# Sinewave_PWM_controller.net
KiCad netlist of a schematic drawn in Altium Designer
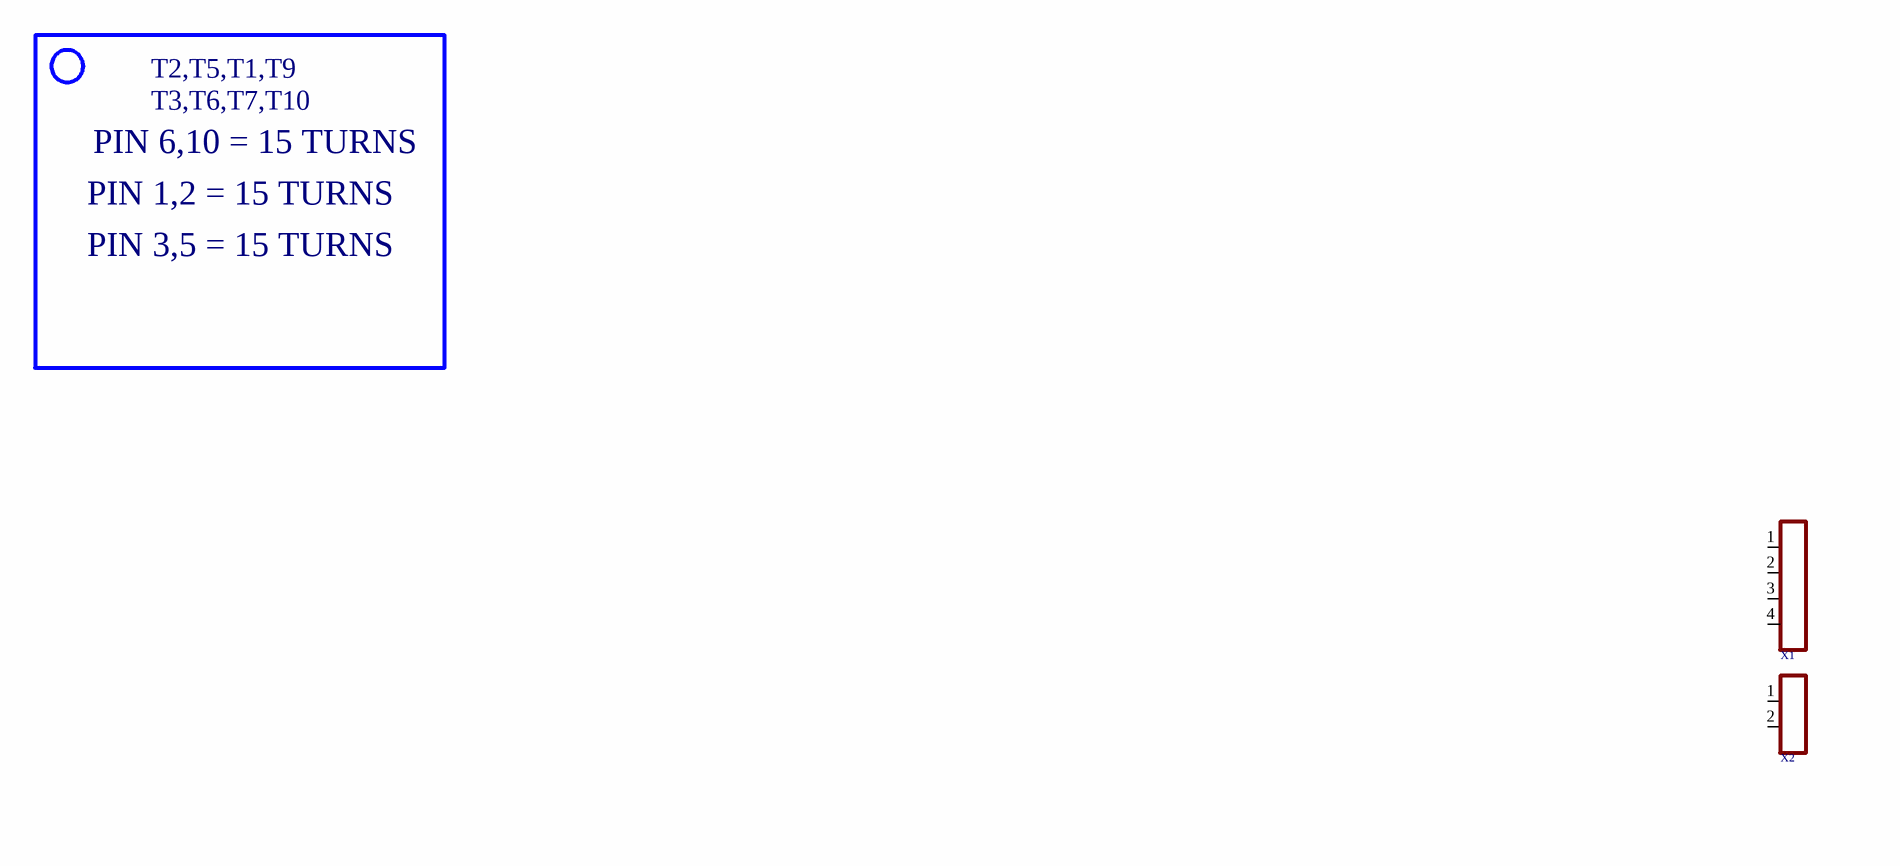
[diagram p0: Sinewave PWM controller.SchDoc, left]
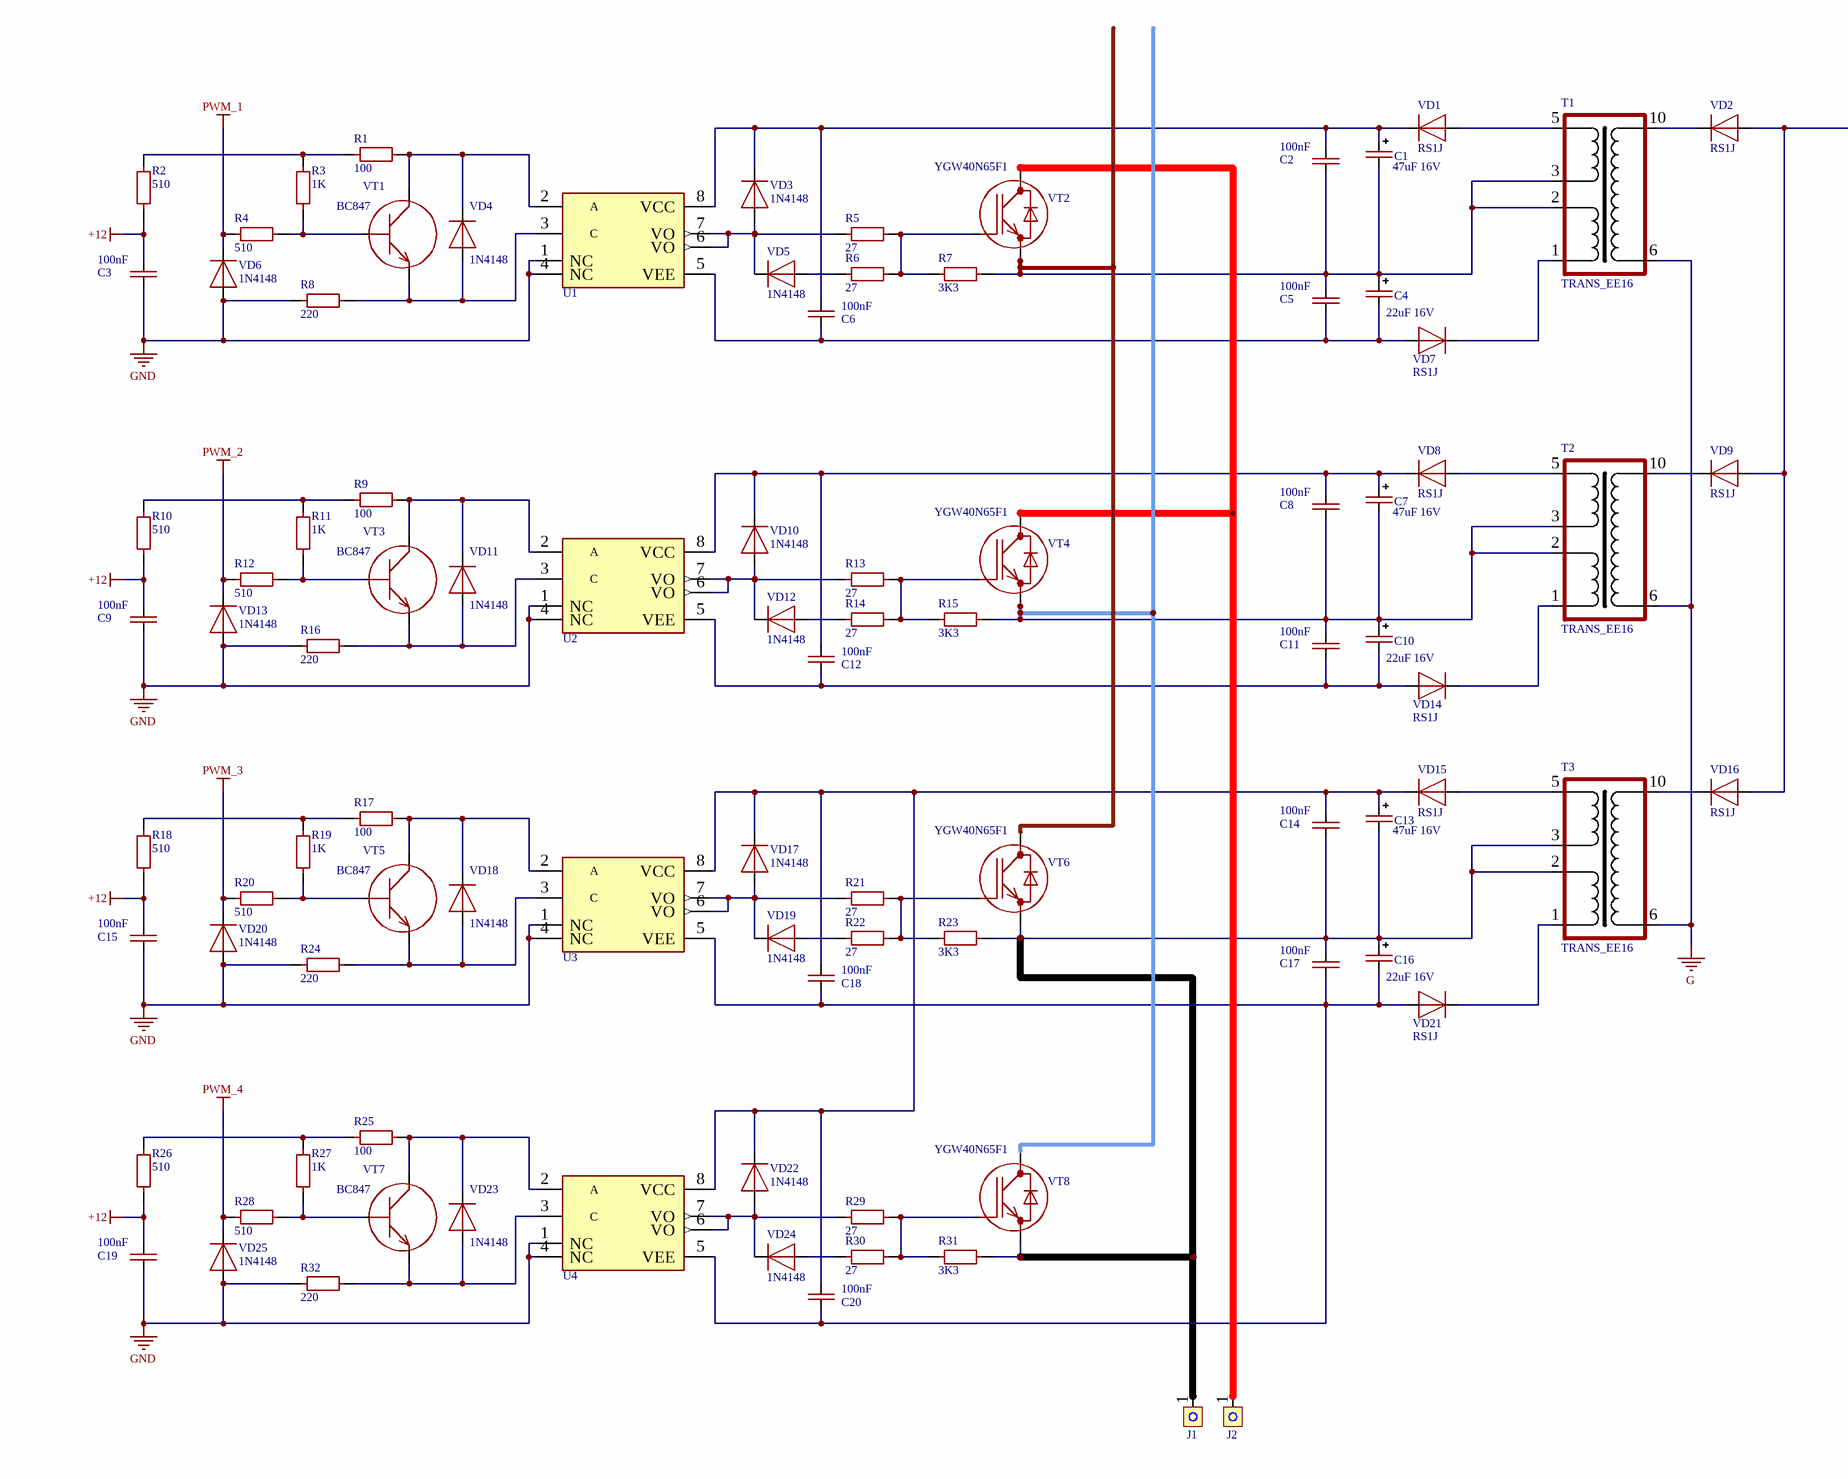
[diagram p1: Sinewave PWM controller.SchDoc, right]

(export (version "E")
  (design (tool "Eeschema 10.0.6"))
  (components
    (comp (ref "C1")
      (value "47uF 16V")
      (footprint "CAP-TAN-C")
      (libsource (lib "PAS_COMPONENTS") (part "CAP-POLAR"))
    )
    (comp (ref "C2")
      (value "100nF")
      (footprint "CAP-1206")
      (libsource (lib "PAS_COMPONENTS") (part "CAP-NON-POLAR"))
    )
    (comp (ref "C3")
      (value "100nF")
      (footprint "CAP-1206")
      (libsource (lib "PAS_COMPONENTS") (part "CAP-NON-POLAR"))
    )
    (comp (ref "C4")
      (value "22uF 16V")
      (footprint "CAP-TAN-C")
      (libsource (lib "PAS_COMPONENTS") (part "CAP-POLAR"))
    )
    (comp (ref "C5")
      (value "100nF")
      (footprint "CAP-1206")
      (libsource (lib "PAS_COMPONENTS") (part "CAP-NON-POLAR"))
    )
    (comp (ref "C6")
      (value "100nF")
      (footprint "CAP-1206")
      (libsource (lib "PAS_COMPONENTS") (part "CAP-NON-POLAR"))
    )
    (comp (ref "C7")
      (value "47uF 16V")
      (footprint "CAP-TAN-C")
      (libsource (lib "PAS_COMPONENTS") (part "CAP-POLAR"))
    )
    (comp (ref "C8")
      (value "100nF")
      (footprint "CAP-1206")
      (libsource (lib "PAS_COMPONENTS") (part "CAP-NON-POLAR"))
    )
    (comp (ref "C9")
      (value "100nF")
      (footprint "CAP-1206")
      (libsource (lib "PAS_COMPONENTS") (part "CAP-NON-POLAR"))
    )
    (comp (ref "C10")
      (value "22uF 16V")
      (footprint "CAP-TAN-C")
      (libsource (lib "PAS_COMPONENTS") (part "CAP-POLAR"))
    )
    (comp (ref "C11")
      (value "100nF")
      (footprint "CAP-1206")
      (libsource (lib "PAS_COMPONENTS") (part "CAP-NON-POLAR"))
    )
    (comp (ref "C12")
      (value "100nF")
      (footprint "CAP-1206")
      (libsource (lib "PAS_COMPONENTS") (part "CAP-NON-POLAR"))
    )
    (comp (ref "C13")
      (value "47uF 16V")
      (footprint "CAP-TAN-C")
      (libsource (lib "PAS_COMPONENTS") (part "CAP-POLAR"))
    )
    (comp (ref "C14")
      (value "100nF")
      (footprint "CAP-1206")
      (libsource (lib "PAS_COMPONENTS") (part "CAP-NON-POLAR"))
    )
    (comp (ref "C15")
      (value "100nF")
      (footprint "CAP-1206")
      (libsource (lib "PAS_COMPONENTS") (part "CAP-NON-POLAR"))
    )
    (comp (ref "C16")
      (value "22uF 16V")
      (footprint "CAP-TAN-C")
      (libsource (lib "PAS_COMPONENTS") (part "CAP-POLAR"))
    )
    (comp (ref "C17")
      (value "100nF")
      (footprint "CAP-1206")
      (libsource (lib "PAS_COMPONENTS") (part "CAP-NON-POLAR"))
    )
    (comp (ref "C18")
      (value "100nF")
      (footprint "CAP-1206")
      (libsource (lib "PAS_COMPONENTS") (part "CAP-NON-POLAR"))
    )
    (comp (ref "C19")
      (value "100nF")
      (footprint "CAP-1206")
      (libsource (lib "PAS_COMPONENTS") (part "CAP-NON-POLAR"))
    )
    (comp (ref "C20")
      (value "100nF")
      (footprint "CAP-1206")
      (libsource (lib "PAS_COMPONENTS") (part "CAP-NON-POLAR"))
    )
    (comp (ref "J1")
      (value "MG_136_HT")
      (footprint "Conn_MEIGAN_MG136HT")
      (libsource (lib "Connectors") (part "Connector_MEIGAN_MG136HT"))
    )
    (comp (ref "J2")
      (value "MG_136_HT")
      (footprint "Conn_MEIGAN_MG136HT")
      (libsource (lib "Connectors") (part "Connector_MEIGAN_MG136HT"))
    )
    (comp (ref "R1")
      (value "100")
      (footprint "RES-0805")
      (libsource (lib "PAS_COMPONENTS") (part "RES-CONST"))
    )
    (comp (ref "R2")
      (value "510")
      (footprint "RES-0805")
      (libsource (lib "PAS_COMPONENTS") (part "RES-CONST"))
    )
    (comp (ref "R3")
      (value "1K")
      (footprint "RES-0805")
      (libsource (lib "PAS_COMPONENTS") (part "RES-CONST"))
    )
    (comp (ref "R4")
      (value "510")
      (footprint "RES-0805")
      (libsource (lib "PAS_COMPONENTS") (part "RES-CONST"))
    )
    (comp (ref "R5")
      (value "27")
      (footprint "RES-0805")
      (libsource (lib "PAS_COMPONENTS") (part "RES-CONST"))
    )
    (comp (ref "R6")
      (value "27")
      (footprint "RES-0805")
      (libsource (lib "PAS_COMPONENTS") (part "RES-CONST"))
    )
    (comp (ref "R7")
      (value "3K3")
      (footprint "RES-0805")
      (libsource (lib "PAS_COMPONENTS") (part "RES-CONST"))
    )
    (comp (ref "R8")
      (value "220")
      (footprint "RES-0805")
      (libsource (lib "PAS_COMPONENTS") (part "RES-CONST"))
    )
    (comp (ref "R9")
      (value "100")
      (footprint "RES-0805")
      (libsource (lib "PAS_COMPONENTS") (part "RES-CONST"))
    )
    (comp (ref "R10")
      (value "510")
      (footprint "RES-0805")
      (libsource (lib "PAS_COMPONENTS") (part "RES-CONST"))
    )
    (comp (ref "R11")
      (value "1K")
      (footprint "RES-0805")
      (libsource (lib "PAS_COMPONENTS") (part "RES-CONST"))
    )
    (comp (ref "R12")
      (value "510")
      (footprint "RES-0805")
      (libsource (lib "PAS_COMPONENTS") (part "RES-CONST"))
    )
    (comp (ref "R13")
      (value "27")
      (footprint "RES-0805")
      (libsource (lib "PAS_COMPONENTS") (part "RES-CONST"))
    )
    (comp (ref "R14")
      (value "27")
      (footprint "RES-0805")
      (libsource (lib "PAS_COMPONENTS") (part "RES-CONST"))
    )
    (comp (ref "R15")
      (value "3K3")
      (footprint "RES-0805")
      (libsource (lib "PAS_COMPONENTS") (part "RES-CONST"))
    )
    (comp (ref "R16")
      (value "220")
      (footprint "RES-0805")
      (libsource (lib "PAS_COMPONENTS") (part "RES-CONST"))
    )
    (comp (ref "R17")
      (value "100")
      (footprint "RES-0805")
      (libsource (lib "PAS_COMPONENTS") (part "RES-CONST"))
    )
    (comp (ref "R18")
      (value "510")
      (footprint "RES-0805")
      (libsource (lib "PAS_COMPONENTS") (part "RES-CONST"))
    )
    (comp (ref "R19")
      (value "1K")
      (footprint "RES-0805")
      (libsource (lib "PAS_COMPONENTS") (part "RES-CONST"))
    )
    (comp (ref "R20")
      (value "510")
      (footprint "RES-0805")
      (libsource (lib "PAS_COMPONENTS") (part "RES-CONST"))
    )
    (comp (ref "R21")
      (value "27")
      (footprint "RES-0805")
      (libsource (lib "PAS_COMPONENTS") (part "RES-CONST"))
    )
    (comp (ref "R22")
      (value "27")
      (footprint "RES-0805")
      (libsource (lib "PAS_COMPONENTS") (part "RES-CONST"))
    )
    (comp (ref "R23")
      (value "3K3")
      (footprint "RES-0805")
      (libsource (lib "PAS_COMPONENTS") (part "RES-CONST"))
    )
    (comp (ref "R24")
      (value "220")
      (footprint "RES-0805")
      (libsource (lib "PAS_COMPONENTS") (part "RES-CONST"))
    )
    (comp (ref "R25")
      (value "100")
      (footprint "RES-0805")
      (libsource (lib "PAS_COMPONENTS") (part "RES-CONST"))
    )
    (comp (ref "R26")
      (value "510")
      (footprint "RES-0805")
      (libsource (lib "PAS_COMPONENTS") (part "RES-CONST"))
    )
    (comp (ref "R27")
      (value "1K")
      (footprint "RES-0805")
      (libsource (lib "PAS_COMPONENTS") (part "RES-CONST"))
    )
    (comp (ref "R28")
      (value "510")
      (footprint "RES-0805")
      (libsource (lib "PAS_COMPONENTS") (part "RES-CONST"))
    )
    (comp (ref "R29")
      (value "27")
      (footprint "RES-0805")
      (libsource (lib "PAS_COMPONENTS") (part "RES-CONST"))
    )
    (comp (ref "R30")
      (value "27")
      (footprint "RES-0805")
      (libsource (lib "PAS_COMPONENTS") (part "RES-CONST"))
    )
    (comp (ref "R31")
      (value "3K3")
      (footprint "RES-0805")
      (libsource (lib "PAS_COMPONENTS") (part "RES-CONST"))
    )
    (comp (ref "R32")
      (value "220")
      (footprint "RES-0805")
      (libsource (lib "PAS_COMPONENTS") (part "RES-CONST"))
    )
    (comp (ref "T1")
      (value "TRANS_EE16")
      (footprint "TRANS_EE16")
      (libsource (lib "TRANS_EE16") (part "TRANS_EE16"))
    )
    (comp (ref "T2")
      (value "TRANS_EE16")
      (footprint "TRANS_EE16")
      (libsource (lib "TRANS_EE16") (part "TRANS_EE16"))
    )
    (comp (ref "T3")
      (value "TRANS_EE16")
      (footprint "TRANS_EE16")
      (libsource (lib "TRANS_EE16") (part "TRANS_EE16"))
    )
    (comp (ref "U1")
      (value "HCPL-3120")
      (footprint "HCPL-3120")
      (libsource (lib "Integrated_Circuts") (part "HCPL-3120"))
    )
    (comp (ref "U2")
      (value "HCPL-3120")
      (footprint "HCPL-3120")
      (libsource (lib "Integrated_Circuts") (part "HCPL-3120"))
    )
    (comp (ref "U3")
      (value "HCPL-3120")
      (footprint "HCPL-3120")
      (libsource (lib "Integrated_Circuts") (part "HCPL-3120"))
    )
    (comp (ref "U4")
      (value "HCPL-3120")
      (footprint "HCPL-3120")
      (libsource (lib "Integrated_Circuts") (part "HCPL-3120"))
    )
    (comp (ref "VD1") (value "RS1J") (footprint "DO-214AC, SMA") (libsource (lib "DIODES") (part "DIODE")))
    (comp (ref "VD2") (value "RS1J") (footprint "DO-214AC, SMA") (libsource (lib "DIODES") (part "DIODE")))
    (comp (ref "VD3") (value "1N4148") (footprint "SOD-123") (libsource (lib "DIODES") (part "DIODE")))
    (comp (ref "VD4") (value "1N4148") (footprint "SOD-123") (libsource (lib "DIODES") (part "DIODE")))
    (comp (ref "VD5") (value "1N4148") (footprint "SOD-123") (libsource (lib "DIODES") (part "DIODE")))
    (comp (ref "VD6") (value "1N4148") (footprint "SOD-123") (libsource (lib "DIODES") (part "DIODE")))
    (comp (ref "VD7") (value "RS1J") (footprint "DO-214AC, SMA") (libsource (lib "DIODES") (part "DIODE")))
    (comp (ref "VD8") (value "RS1J") (footprint "DO-214AC, SMA") (libsource (lib "DIODES") (part "DIODE")))
    (comp (ref "VD9") (value "RS1J") (footprint "DO-214AC, SMA") (libsource (lib "DIODES") (part "DIODE")))
    (comp (ref "VD10") (value "1N4148") (footprint "SOD-123") (libsource (lib "DIODES") (part "DIODE")))
    (comp (ref "VD11") (value "1N4148") (footprint "SOD-123") (libsource (lib "DIODES") (part "DIODE")))
    (comp (ref "VD12") (value "1N4148") (footprint "SOD-123") (libsource (lib "DIODES") (part "DIODE")))
    (comp (ref "VD13") (value "1N4148") (footprint "SOD-123") (libsource (lib "DIODES") (part "DIODE")))
    (comp (ref "VD14") (value "RS1J") (footprint "DO-214AC, SMA") (libsource (lib "DIODES") (part "DIODE")))
    (comp (ref "VD15") (value "RS1J") (footprint "DO-214AC, SMA") (libsource (lib "DIODES") (part "DIODE")))
    (comp (ref "VD16") (value "RS1J") (footprint "DO-214AC, SMA") (libsource (lib "DIODES") (part "DIODE")))
    (comp (ref "VD17") (value "1N4148") (footprint "SOD-123") (libsource (lib "DIODES") (part "DIODE")))
    (comp (ref "VD18") (value "1N4148") (footprint "SOD-123") (libsource (lib "DIODES") (part "DIODE")))
    (comp (ref "VD19") (value "1N4148") (footprint "SOD-123") (libsource (lib "DIODES") (part "DIODE")))
    (comp (ref "VD20") (value "1N4148") (footprint "SOD-123") (libsource (lib "DIODES") (part "DIODE")))
    (comp (ref "VD21") (value "RS1J") (footprint "DO-214AC, SMA") (libsource (lib "DIODES") (part "DIODE")))
    (comp (ref "VD22") (value "1N4148") (footprint "SOD-123") (libsource (lib "DIODES") (part "DIODE")))
    (comp (ref "VD23") (value "1N4148") (footprint "SOD-123") (libsource (lib "DIODES") (part "DIODE")))
    (comp (ref "VD24") (value "1N4148") (footprint "SOD-123") (libsource (lib "DIODES") (part "DIODE")))
    (comp (ref "VD25") (value "1N4148") (footprint "SOD-123") (libsource (lib "DIODES") (part "DIODE")))
    (comp (ref "VT1")
      (value "BC847")
      (footprint "SOT23-3")
      (libsource (lib "TRANSISTORS") (part "BIPOLAR-NPN-BEC"))
    )
    (comp (ref "VT2")
      (value "YGW40N65F1")
      (footprint "TO-247-3")
      (libsource (lib "TRANSISTORS") (part "IGBT-N-GCE"))
    )
    (comp (ref "VT3")
      (value "BC847")
      (footprint "SOT23-3")
      (libsource (lib "TRANSISTORS") (part "BIPOLAR-NPN-BEC"))
    )
    (comp (ref "VT4")
      (value "YGW40N65F1")
      (footprint "TO-247-3")
      (libsource (lib "TRANSISTORS") (part "IGBT-N-GCE"))
    )
    (comp (ref "VT5")
      (value "BC847")
      (footprint "SOT23-3")
      (libsource (lib "TRANSISTORS") (part "BIPOLAR-NPN-BEC"))
    )
    (comp (ref "VT6")
      (value "YGW40N65F1")
      (footprint "TO-247-3")
      (libsource (lib "TRANSISTORS") (part "IGBT-N-GCE"))
    )
    (comp (ref "VT7")
      (value "BC847")
      (footprint "SOT23-3")
      (libsource (lib "TRANSISTORS") (part "BIPOLAR-NPN-BEC"))
    )
    (comp (ref "VT8")
      (value "YGW40N65F1")
      (footprint "TO-247-3")
      (libsource (lib "TRANSISTORS") (part "IGBT-N-GCE"))
    )
    (comp (ref "X1")
      (value "CONN-4-PIN")
      (footprint "CONN-PLS-4-2.54mm_1")
      (libsource (lib "XH 4PIN") (part "CONN-4-PIN"))
    )
    (comp (ref "X2") (value "CONN-2-PIN") (footprint "XH2-") (libsource (lib "XH 2PIN") (part "CONN-2-PIN")))
  )
  (nets
    (net (code "1") (name "+12") (class "Default")
      (node (ref "C15") (pin "2") (pinfunction "2_2") (pintype "passive"))
      (node (ref "C19") (pin "2") (pinfunction "2_2") (pintype "passive"))
      (node (ref "C3") (pin "2") (pinfunction "2_2") (pintype "passive"))
      (node (ref "C9") (pin "2") (pinfunction "2_2") (pintype "passive"))
      (node (ref "R10") (pin "2") (pinfunction "2_2") (pintype "passive"))
      (node (ref "R18") (pin "2") (pinfunction "2_2") (pintype "passive"))
      (node (ref "R2") (pin "2") (pinfunction "2_2") (pintype "passive"))
      (node (ref "R26") (pin "2") (pinfunction "2_2") (pintype "passive"))
    )
    (net (code "2") (name "G") (class "Default")
      (node (ref "T1") (pin "6") (pintype "passive"))
      (node (ref "T2") (pin "6") (pintype "passive"))
      (node (ref "T3") (pin "6") (pintype "passive"))
    )
    (net (code "3") (name "GND") (class "Default")
      (node (ref "C15") (pin "1") (pinfunction "1_1") (pintype "passive"))
      (node (ref "C19") (pin "1") (pinfunction "1_1") (pintype "passive"))
      (node (ref "C3") (pin "1") (pinfunction "1_1") (pintype "passive"))
      (node (ref "C9") (pin "1") (pinfunction "1_1") (pintype "passive"))
      (node (ref "R16") (pin "1") (pinfunction "1_1") (pintype "passive"))
      (node (ref "R24") (pin "1") (pinfunction "1_1") (pintype "passive"))
      (node (ref "R32") (pin "1") (pinfunction "1_1") (pintype "passive"))
      (node (ref "R8") (pin "1") (pinfunction "1_1") (pintype "passive"))
      (node (ref "U1") (pin "1") (pinfunction "NC_1") (pintype "passive"))
      (node (ref "U1") (pin "4") (pinfunction "NC_4") (pintype "passive"))
      (node (ref "U2") (pin "1") (pinfunction "NC_1") (pintype "passive"))
      (node (ref "U2") (pin "4") (pinfunction "NC_4") (pintype "passive"))
      (node (ref "U3") (pin "1") (pinfunction "NC_1") (pintype "passive"))
      (node (ref "U3") (pin "4") (pinfunction "NC_4") (pintype "passive"))
      (node (ref "U4") (pin "1") (pinfunction "NC_1") (pintype "passive"))
      (node (ref "U4") (pin "4") (pinfunction "NC_4") (pintype "passive"))
      (node (ref "VD13") (pin "2") (pinfunction "A_2") (pintype "passive"))
      (node (ref "VD20") (pin "2") (pinfunction "A_2") (pintype "passive"))
      (node (ref "VD25") (pin "2") (pinfunction "A_2") (pintype "passive"))
      (node (ref "VD6") (pin "2") (pinfunction "A_2") (pintype "passive"))
    )
    (net (code "4") (name "Net-(C1-+)") (class "Default")
      (node (ref "C1") (pin "1") (pinfunction "+_1") (pintype "passive"))
      (node (ref "C2") (pin "2") (pinfunction "2_2") (pintype "passive"))
      (node (ref "C6") (pin "2") (pinfunction "2_2") (pintype "passive"))
      (node (ref "U1") (pin "8") (pinfunction "VCC_8") (pintype "power_in"))
      (node (ref "VD1") (pin "1") (pinfunction "C_1") (pintype "passive"))
      (node (ref "VD3") (pin "1") (pinfunction "C_1") (pintype "passive"))
    )
    (net (code "5") (name "Net-(C1--)") (class "Default")
      (node (ref "C1") (pin "2") (pinfunction "-_2") (pintype "passive"))
      (node (ref "C2") (pin "1") (pinfunction "1_1") (pintype "passive"))
      (node (ref "C4") (pin "1") (pinfunction "+_1") (pintype "passive"))
      (node (ref "C5") (pin "2") (pinfunction "2_2") (pintype "passive"))
      (node (ref "R7") (pin "2") (pinfunction "2_2") (pintype "passive"))
      (node (ref "T1") (pin "2") (pintype "passive"))
      (node (ref "T1") (pin "3") (pintype "passive"))
      (node (ref "VT2") (pin "3") (pinfunction "E_3") (pintype "passive"))
      (node (ref "VT6") (pin "2") (pinfunction "C_2") (pintype "passive"))
    )
    (net (code "6") (name "Net-(C4--)") (class "Default")
      (node (ref "C4") (pin "2") (pinfunction "-_2") (pintype "passive"))
      (node (ref "C5") (pin "1") (pinfunction "1_1") (pintype "passive"))
      (node (ref "C6") (pin "1") (pinfunction "1_1") (pintype "passive"))
      (node (ref "U1") (pin "5") (pinfunction "VEE_5") (pintype "power_in"))
      (node (ref "VD7") (pin "2") (pinfunction "A_2") (pintype "passive"))
    )
    (net (code "7") (name "Net-(C7-+)") (class "Default")
      (node (ref "C12") (pin "2") (pinfunction "2_2") (pintype "passive"))
      (node (ref "C7") (pin "1") (pinfunction "+_1") (pintype "passive"))
      (node (ref "C8") (pin "2") (pinfunction "2_2") (pintype "passive"))
      (node (ref "U2") (pin "8") (pinfunction "VCC_8") (pintype "power_in"))
      (node (ref "VD10") (pin "1") (pinfunction "C_1") (pintype "passive"))
      (node (ref "VD8") (pin "1") (pinfunction "C_1") (pintype "passive"))
    )
    (net (code "8") (name "Net-(C10-+)") (class "Default")
      (node (ref "C10") (pin "1") (pinfunction "+_1") (pintype "passive"))
      (node (ref "C11") (pin "2") (pinfunction "2_2") (pintype "passive"))
      (node (ref "C7") (pin "2") (pinfunction "-_2") (pintype "passive"))
      (node (ref "C8") (pin "1") (pinfunction "1_1") (pintype "passive"))
      (node (ref "R15") (pin "2") (pinfunction "2_2") (pintype "passive"))
      (node (ref "T2") (pin "2") (pintype "passive"))
      (node (ref "T2") (pin "3") (pintype "passive"))
      (node (ref "VT4") (pin "3") (pinfunction "E_3") (pintype "passive"))
      (node (ref "VT8") (pin "2") (pinfunction "C_2") (pintype "passive"))
    )
    (net (code "9") (name "Net-(C10--)") (class "Default")
      (node (ref "C10") (pin "2") (pinfunction "-_2") (pintype "passive"))
      (node (ref "C11") (pin "1") (pinfunction "1_1") (pintype "passive"))
      (node (ref "C12") (pin "1") (pinfunction "1_1") (pintype "passive"))
      (node (ref "U2") (pin "5") (pinfunction "VEE_5") (pintype "power_in"))
      (node (ref "VD14") (pin "2") (pinfunction "A_2") (pintype "passive"))
    )
    (net (code "10") (name "Net-(C13-+)") (class "Default")
      (node (ref "C13") (pin "1") (pinfunction "+_1") (pintype "passive"))
      (node (ref "C14") (pin "2") (pinfunction "2_2") (pintype "passive"))
      (node (ref "C18") (pin "2") (pinfunction "2_2") (pintype "passive"))
      (node (ref "C20") (pin "2") (pinfunction "2_2") (pintype "passive"))
      (node (ref "U3") (pin "8") (pinfunction "VCC_8") (pintype "power_in"))
      (node (ref "U4") (pin "8") (pinfunction "VCC_8") (pintype "power_in"))
      (node (ref "VD15") (pin "1") (pinfunction "C_1") (pintype "passive"))
      (node (ref "VD17") (pin "1") (pinfunction "C_1") (pintype "passive"))
      (node (ref "VD22") (pin "1") (pinfunction "C_1") (pintype "passive"))
    )
    (net (code "11") (name "Net-(C13--)") (class "Default")
      (node (ref "C13") (pin "2") (pinfunction "-_2") (pintype "passive"))
      (node (ref "C14") (pin "1") (pinfunction "1_1") (pintype "passive"))
      (node (ref "C16") (pin "1") (pinfunction "+_1") (pintype "passive"))
      (node (ref "C17") (pin "2") (pinfunction "2_2") (pintype "passive"))
      (node (ref "J1") (pin "1") (pinfunction "17_1") (pintype "passive"))
      (node (ref "R23") (pin "2") (pinfunction "2_2") (pintype "passive"))
      (node (ref "R31") (pin "2") (pinfunction "2_2") (pintype "passive"))
      (node (ref "T3") (pin "2") (pintype "passive"))
      (node (ref "T3") (pin "3") (pintype "passive"))
      (node (ref "VT6") (pin "3") (pinfunction "E_3") (pintype "passive"))
      (node (ref "VT8") (pin "3") (pinfunction "E_3") (pintype "passive"))
    )
    (net (code "12") (name "Net-(C16--)") (class "Default")
      (node (ref "C16") (pin "2") (pinfunction "-_2") (pintype "passive"))
      (node (ref "C17") (pin "1") (pinfunction "1_1") (pintype "passive"))
      (node (ref "C18") (pin "1") (pinfunction "1_1") (pintype "passive"))
      (node (ref "C20") (pin "1") (pinfunction "1_1") (pintype "passive"))
      (node (ref "U3") (pin "5") (pinfunction "VEE_5") (pintype "power_in"))
      (node (ref "U4") (pin "5") (pinfunction "VEE_5") (pintype "power_in"))
      (node (ref "VD21") (pin "2") (pinfunction "A_2") (pintype "passive"))
    )
    (net (code "13") (name "Net-(J2-17)") (class "Default")
      (node (ref "J2") (pin "1") (pinfunction "17_1") (pintype "passive"))
      (node (ref "VT2") (pin "2") (pinfunction "C_2") (pintype "passive"))
      (node (ref "VT4") (pin "2") (pinfunction "C_2") (pintype "passive"))
    )
    (net (code "14") (name "Net-(R1-Pad1)") (class "Default")
      (node (ref "R1") (pin "1") (pinfunction "1_1") (pintype "passive"))
      (node (ref "R2") (pin "1") (pinfunction "1_1") (pintype "passive"))
      (node (ref "R3") (pin "2") (pinfunction "2_2") (pintype "passive"))
    )
    (net (code "15") (name "Net-(R10-Pad1)") (class "Default")
      (node (ref "R10") (pin "1") (pinfunction "1_1") (pintype "passive"))
      (node (ref "R11") (pin "2") (pinfunction "2_2") (pintype "passive"))
      (node (ref "R9") (pin "1") (pinfunction "1_1") (pintype "passive"))
    )
    (net (code "16") (name "Net-(R17-Pad1)") (class "Default")
      (node (ref "R17") (pin "1") (pinfunction "1_1") (pintype "passive"))
      (node (ref "R18") (pin "1") (pinfunction "1_1") (pintype "passive"))
      (node (ref "R19") (pin "2") (pinfunction "2_2") (pintype "passive"))
    )
    (net (code "17") (name "Net-(R25-Pad1)") (class "Default")
      (node (ref "R25") (pin "1") (pinfunction "1_1") (pintype "passive"))
      (node (ref "R26") (pin "1") (pinfunction "1_1") (pintype "passive"))
      (node (ref "R27") (pin "2") (pinfunction "2_2") (pintype "passive"))
    )
    (net (code "18") (name "Net-(U1-A)") (class "Default")
      (node (ref "R1") (pin "2") (pinfunction "2_2") (pintype "passive"))
      (node (ref "U1") (pin "2") (pinfunction "A_2") (pintype "passive"))
      (node (ref "VD4") (pin "1") (pinfunction "C_1") (pintype "passive"))
      (node (ref "VT1") (pin "2") (pinfunction "C_2") (pintype "passive"))
    )
    (net (code "19") (name "Net-(U1-C)") (class "Default")
      (node (ref "R8") (pin "2") (pinfunction "2_2") (pintype "passive"))
      (node (ref "U1") (pin "3") (pinfunction "C_3") (pintype "passive"))
      (node (ref "VD4") (pin "2") (pinfunction "A_2") (pintype "passive"))
      (node (ref "VT1") (pin "3") (pinfunction "E_3") (pintype "passive"))
    )
    (net (code "20") (name "Net-(U2-A)") (class "Default")
      (node (ref "R9") (pin "2") (pinfunction "2_2") (pintype "passive"))
      (node (ref "U2") (pin "2") (pinfunction "A_2") (pintype "passive"))
      (node (ref "VD11") (pin "1") (pinfunction "C_1") (pintype "passive"))
      (node (ref "VT3") (pin "2") (pinfunction "C_2") (pintype "passive"))
    )
    (net (code "21") (name "Net-(U2-C)") (class "Default")
      (node (ref "R16") (pin "2") (pinfunction "2_2") (pintype "passive"))
      (node (ref "U2") (pin "3") (pinfunction "C_3") (pintype "passive"))
      (node (ref "VD11") (pin "2") (pinfunction "A_2") (pintype "passive"))
      (node (ref "VT3") (pin "3") (pinfunction "E_3") (pintype "passive"))
    )
    (net (code "22") (name "Net-(U3-A)") (class "Default")
      (node (ref "R17") (pin "2") (pinfunction "2_2") (pintype "passive"))
      (node (ref "U3") (pin "2") (pinfunction "A_2") (pintype "passive"))
      (node (ref "VD18") (pin "1") (pinfunction "C_1") (pintype "passive"))
      (node (ref "VT5") (pin "2") (pinfunction "C_2") (pintype "passive"))
    )
    (net (code "23") (name "Net-(U3-C)") (class "Default")
      (node (ref "R24") (pin "2") (pinfunction "2_2") (pintype "passive"))
      (node (ref "U3") (pin "3") (pinfunction "C_3") (pintype "passive"))
      (node (ref "VD18") (pin "2") (pinfunction "A_2") (pintype "passive"))
      (node (ref "VT5") (pin "3") (pinfunction "E_3") (pintype "passive"))
    )
    (net (code "24") (name "Net-(U4-A)") (class "Default")
      (node (ref "R25") (pin "2") (pinfunction "2_2") (pintype "passive"))
      (node (ref "U4") (pin "2") (pinfunction "A_2") (pintype "passive"))
      (node (ref "VD23") (pin "1") (pinfunction "C_1") (pintype "passive"))
      (node (ref "VT7") (pin "2") (pinfunction "C_2") (pintype "passive"))
    )
    (net (code "25") (name "Net-(U4-C)") (class "Default")
      (node (ref "R32") (pin "2") (pinfunction "2_2") (pintype "passive"))
      (node (ref "U4") (pin "3") (pinfunction "C_3") (pintype "passive"))
      (node (ref "VD23") (pin "2") (pinfunction "A_2") (pintype "passive"))
      (node (ref "VT7") (pin "3") (pinfunction "E_3") (pintype "passive"))
    )
    (net (code "26") (name "Net-(VD1-A)") (class "Default")
      (node (ref "T1") (pin "5") (pintype "passive"))
      (node (ref "VD1") (pin "2") (pinfunction "A_2") (pintype "passive"))
    )
    (net (code "27") (name "Net-(VD2-C)") (class "Default")
      (node (ref "T1") (pin "10") (pintype "passive"))
      (node (ref "VD2") (pin "1") (pinfunction "C_1") (pintype "passive"))
    )
    (net (code "28") (name "Net-(VD3-A)") (class "Default")
      (node (ref "R5") (pin "1") (pinfunction "1_1") (pintype "passive"))
      (node (ref "U1") (pin "6") (pinfunction "VO_6") (pintype "output"))
      (node (ref "U1") (pin "7") (pinfunction "VO_7") (pintype "output"))
      (node (ref "VD3") (pin "2") (pinfunction "A_2") (pintype "passive"))
      (node (ref "VD5") (pin "1") (pinfunction "C_1") (pintype "passive"))
    )
    (net (code "29") (name "Net-(VD5-A)") (class "Default")
      (node (ref "R6") (pin "1") (pinfunction "1_1") (pintype "passive"))
      (node (ref "VD5") (pin "2") (pinfunction "A_2") (pintype "passive"))
    )
    (net (code "30") (name "Net-(VD7-C)") (class "Default")
      (node (ref "T1") (pin "1") (pintype "passive"))
      (node (ref "VD7") (pin "1") (pinfunction "C_1") (pintype "passive"))
    )
    (net (code "31") (name "Net-(VD8-A)") (class "Default")
      (node (ref "T2") (pin "5") (pintype "passive"))
      (node (ref "VD8") (pin "2") (pinfunction "A_2") (pintype "passive"))
    )
    (net (code "32") (name "Net-(VD9-C)") (class "Default")
      (node (ref "T2") (pin "10") (pintype "passive"))
      (node (ref "VD9") (pin "1") (pinfunction "C_1") (pintype "passive"))
    )
    (net (code "33") (name "Net-(VD10-A)") (class "Default")
      (node (ref "R13") (pin "1") (pinfunction "1_1") (pintype "passive"))
      (node (ref "U2") (pin "6") (pinfunction "VO_6") (pintype "output"))
      (node (ref "U2") (pin "7") (pinfunction "VO_7") (pintype "output"))
      (node (ref "VD10") (pin "2") (pinfunction "A_2") (pintype "passive"))
      (node (ref "VD12") (pin "1") (pinfunction "C_1") (pintype "passive"))
    )
    (net (code "34") (name "Net-(VD12-A)") (class "Default")
      (node (ref "R14") (pin "1") (pinfunction "1_1") (pintype "passive"))
      (node (ref "VD12") (pin "2") (pinfunction "A_2") (pintype "passive"))
    )
    (net (code "35") (name "Net-(VD14-C)") (class "Default")
      (node (ref "T2") (pin "1") (pintype "passive"))
      (node (ref "VD14") (pin "1") (pinfunction "C_1") (pintype "passive"))
    )
    (net (code "36") (name "Net-(VD15-A)") (class "Default")
      (node (ref "T3") (pin "5") (pintype "passive"))
      (node (ref "VD15") (pin "2") (pinfunction "A_2") (pintype "passive"))
    )
    (net (code "37") (name "Net-(VD16-A)") (class "Default")
      (node (ref "VD16") (pin "2") (pinfunction "A_2") (pintype "passive"))
      (node (ref "VD2") (pin "2") (pinfunction "A_2") (pintype "passive"))
      (node (ref "VD9") (pin "2") (pinfunction "A_2") (pintype "passive"))
    )
    (net (code "38") (name "Net-(VD16-C)") (class "Default")
      (node (ref "T3") (pin "10") (pintype "passive"))
      (node (ref "VD16") (pin "1") (pinfunction "C_1") (pintype "passive"))
    )
    (net (code "39") (name "Net-(VD17-A)") (class "Default")
      (node (ref "R21") (pin "1") (pinfunction "1_1") (pintype "passive"))
      (node (ref "U3") (pin "6") (pinfunction "VO_6") (pintype "output"))
      (node (ref "U3") (pin "7") (pinfunction "VO_7") (pintype "output"))
      (node (ref "VD17") (pin "2") (pinfunction "A_2") (pintype "passive"))
      (node (ref "VD19") (pin "1") (pinfunction "C_1") (pintype "passive"))
    )
    (net (code "40") (name "Net-(VD19-A)") (class "Default")
      (node (ref "R22") (pin "1") (pinfunction "1_1") (pintype "passive"))
      (node (ref "VD19") (pin "2") (pinfunction "A_2") (pintype "passive"))
    )
    (net (code "41") (name "Net-(VD21-C)") (class "Default")
      (node (ref "T3") (pin "1") (pintype "passive"))
      (node (ref "VD21") (pin "1") (pinfunction "C_1") (pintype "passive"))
    )
    (net (code "42") (name "Net-(VD22-A)") (class "Default")
      (node (ref "R29") (pin "1") (pinfunction "1_1") (pintype "passive"))
      (node (ref "U4") (pin "6") (pinfunction "VO_6") (pintype "output"))
      (node (ref "U4") (pin "7") (pinfunction "VO_7") (pintype "output"))
      (node (ref "VD22") (pin "2") (pinfunction "A_2") (pintype "passive"))
      (node (ref "VD24") (pin "1") (pinfunction "C_1") (pintype "passive"))
    )
    (net (code "43") (name "Net-(VD24-A)") (class "Default")
      (node (ref "R30") (pin "1") (pinfunction "1_1") (pintype "passive"))
      (node (ref "VD24") (pin "2") (pinfunction "A_2") (pintype "passive"))
    )
    (net (code "44") (name "Net-(VT1-B)") (class "Default")
      (node (ref "R3") (pin "1") (pinfunction "1_1") (pintype "passive"))
      (node (ref "R4") (pin "2") (pinfunction "2_2") (pintype "passive"))
      (node (ref "VT1") (pin "1") (pinfunction "B_1") (pintype "passive"))
    )
    (net (code "45") (name "Net-(VT2-G)") (class "Default")
      (node (ref "R5") (pin "2") (pinfunction "2_2") (pintype "passive"))
      (node (ref "R6") (pin "2") (pinfunction "2_2") (pintype "passive"))
      (node (ref "R7") (pin "1") (pinfunction "1_1") (pintype "passive"))
      (node (ref "VT2") (pin "1") (pinfunction "G_1") (pintype "passive"))
    )
    (net (code "46") (name "Net-(VT3-B)") (class "Default")
      (node (ref "R11") (pin "1") (pinfunction "1_1") (pintype "passive"))
      (node (ref "R12") (pin "2") (pinfunction "2_2") (pintype "passive"))
      (node (ref "VT3") (pin "1") (pinfunction "B_1") (pintype "passive"))
    )
    (net (code "47") (name "Net-(VT4-G)") (class "Default")
      (node (ref "R13") (pin "2") (pinfunction "2_2") (pintype "passive"))
      (node (ref "R14") (pin "2") (pinfunction "2_2") (pintype "passive"))
      (node (ref "R15") (pin "1") (pinfunction "1_1") (pintype "passive"))
      (node (ref "VT4") (pin "1") (pinfunction "G_1") (pintype "passive"))
    )
    (net (code "48") (name "Net-(VT5-B)") (class "Default")
      (node (ref "R19") (pin "1") (pinfunction "1_1") (pintype "passive"))
      (node (ref "R20") (pin "2") (pinfunction "2_2") (pintype "passive"))
      (node (ref "VT5") (pin "1") (pinfunction "B_1") (pintype "passive"))
    )
    (net (code "49") (name "Net-(VT6-G)") (class "Default")
      (node (ref "R21") (pin "2") (pinfunction "2_2") (pintype "passive"))
      (node (ref "R22") (pin "2") (pinfunction "2_2") (pintype "passive"))
      (node (ref "R23") (pin "1") (pinfunction "1_1") (pintype "passive"))
      (node (ref "VT6") (pin "1") (pinfunction "G_1") (pintype "passive"))
    )
    (net (code "50") (name "Net-(VT7-B)") (class "Default")
      (node (ref "R27") (pin "1") (pinfunction "1_1") (pintype "passive"))
      (node (ref "R28") (pin "2") (pinfunction "2_2") (pintype "passive"))
      (node (ref "VT7") (pin "1") (pinfunction "B_1") (pintype "passive"))
    )
    (net (code "51") (name "Net-(VT8-G)") (class "Default")
      (node (ref "R29") (pin "2") (pinfunction "2_2") (pintype "passive"))
      (node (ref "R30") (pin "2") (pinfunction "2_2") (pintype "passive"))
      (node (ref "R31") (pin "1") (pinfunction "1_1") (pintype "passive"))
      (node (ref "VT8") (pin "1") (pinfunction "G_1") (pintype "passive"))
    )
    (net (code "52") (name "PWM_1") (class "Default")
      (node (ref "R4") (pin "1") (pinfunction "1_1") (pintype "passive"))
      (node (ref "VD6") (pin "1") (pinfunction "C_1") (pintype "passive"))
    )
    (net (code "53") (name "PWM_2") (class "Default")
      (node (ref "R12") (pin "1") (pinfunction "1_1") (pintype "passive"))
      (node (ref "VD13") (pin "1") (pinfunction "C_1") (pintype "passive"))
    )
    (net (code "54") (name "PWM_3") (class "Default")
      (node (ref "R20") (pin "1") (pinfunction "1_1") (pintype "passive"))
      (node (ref "VD20") (pin "1") (pinfunction "C_1") (pintype "passive"))
    )
    (net (code "55") (name "PWM_4") (class "Default")
      (node (ref "R28") (pin "1") (pinfunction "1_1") (pintype "passive"))
      (node (ref "VD25") (pin "1") (pinfunction "C_1") (pintype "passive"))
    )
    (net (code "56") (name "unconnected-(X1-Pad1)") (class "Default")
      (node (ref "X1") (pin "1") (pinfunction "1_1") (pintype "passive"))
    )
    (net (code "57") (name "unconnected-(X1-Pad2)") (class "Default")
      (node (ref "X1") (pin "2") (pinfunction "2_2") (pintype "passive"))
    )
    (net (code "58") (name "unconnected-(X1-Pad3)") (class "Default")
      (node (ref "X1") (pin "3") (pinfunction "3_3") (pintype "passive"))
    )
    (net (code "59") (name "unconnected-(X1-Pad4)") (class "Default")
      (node (ref "X1") (pin "4") (pinfunction "4_4") (pintype "passive"))
    )
    (net (code "60") (name "unconnected-(X2-Pad1)") (class "Default")
      (node (ref "X2") (pin "1") (pinfunction "1_1") (pintype "passive"))
    )
    (net (code "61") (name "unconnected-(X2-Pad2)") (class "Default")
      (node (ref "X2") (pin "2") (pinfunction "2_2") (pintype "passive"))
    )
  )
)
